# debugging_board_3.net
KiCad netlist of a schematic drawn in Altium Designer
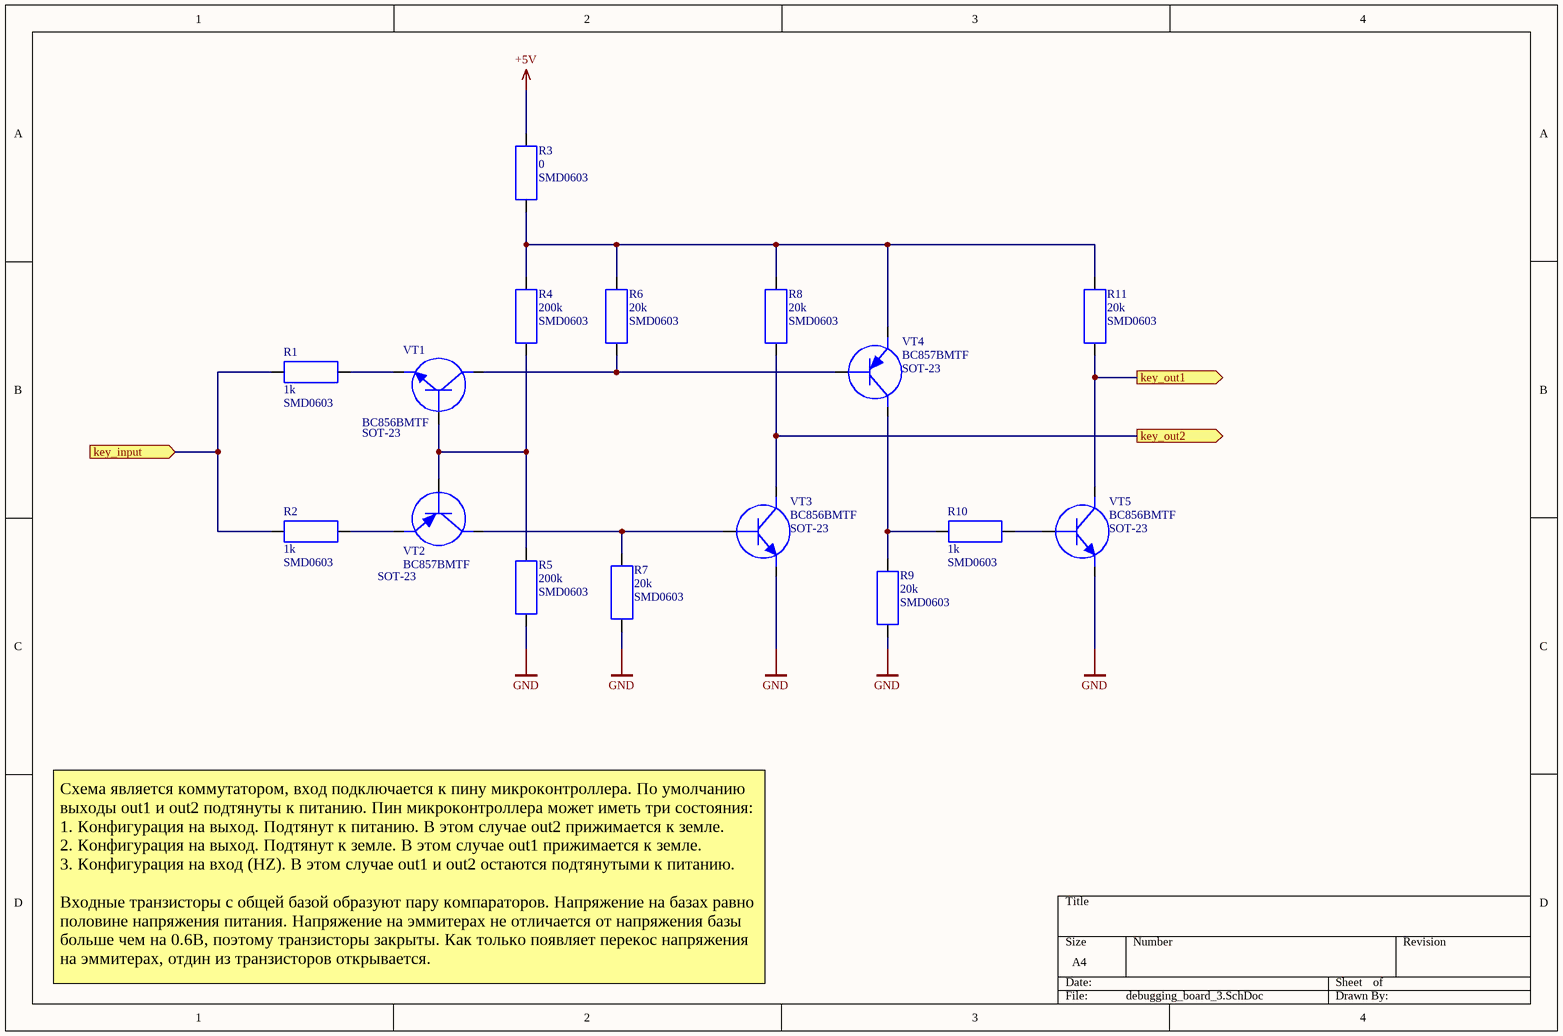
[diagram p0: debugging_board_3.SchDoc]

(export (version "E")
  (design (tool "Eeschema 10.0.6"))
  (components
    (comp (ref "R1")
      (value "1k")
      (footprint "SMD0603(1005)")
      (fields (field (name "PACKAGE") "SMD0603"))
      (libsource (lib "MechanikLibrary") (part "R_0603"))
    )
    (comp (ref "R2")
      (value "1k")
      (footprint "SMD0603(1005)")
      (fields (field (name "PACKAGE") "SMD0603"))
      (libsource (lib "MechanikLibrary") (part "R_0603"))
    )
    (comp (ref "R3")
      (value "0")
      (footprint "SMD0603(1005)")
      (fields (field (name "PACKAGE") "SMD0603"))
      (libsource (lib "MechanikLibrary") (part "R_0603"))
    )
    (comp (ref "R4")
      (value "200k")
      (footprint "SMD0603(1005)")
      (fields (field (name "PACKAGE") "SMD0603"))
      (libsource (lib "MechanikLibrary") (part "R_0603"))
    )
    (comp (ref "R5")
      (value "200k")
      (footprint "SMD0603(1005)")
      (fields (field (name "PACKAGE") "SMD0603"))
      (libsource (lib "MechanikLibrary") (part "R_0603"))
    )
    (comp (ref "R6")
      (value "20k")
      (footprint "SMD0603(1005)")
      (fields (field (name "PACKAGE") "SMD0603"))
      (libsource (lib "MechanikLibrary") (part "R_0603"))
    )
    (comp (ref "R7")
      (value "20k")
      (footprint "SMD0603(1005)")
      (fields (field (name "PACKAGE") "SMD0603"))
      (libsource (lib "MechanikLibrary") (part "R_0603"))
    )
    (comp (ref "R8")
      (value "20k")
      (footprint "SMD0603(1005)")
      (fields (field (name "PACKAGE") "SMD0603"))
      (libsource (lib "MechanikLibrary") (part "R_0603"))
    )
    (comp (ref "R9")
      (value "20k")
      (footprint "SMD0603(1005)")
      (fields (field (name "PACKAGE") "SMD0603"))
      (libsource (lib "MechanikLibrary") (part "R_0603"))
    )
    (comp (ref "R10")
      (value "1k")
      (footprint "SMD0603(1005)")
      (fields (field (name "PACKAGE") "SMD0603"))
      (libsource (lib "MechanikLibrary") (part "R_0603"))
    )
    (comp (ref "R11")
      (value "20k")
      (footprint "SMD0603(1005)")
      (fields (field (name "PACKAGE") "SMD0603"))
      (libsource (lib "MechanikLibrary") (part "R_0603"))
    )
    (comp (ref "VT1")
      (value "BC856BMTF")
      (footprint "SOT23-3")
      (fields (field (name "PACKAGE") "SOT-23"))
      (libsource (lib "MechanikLibrary") (part "VT_NPN_SOT23_3"))
    )
    (comp (ref "VT2")
      (value "BC857BMTF")
      (footprint "SOT23-3")
      (fields (field (name "PACKAGE") "SOT-23"))
      (libsource (lib "MechanikLibrary") (part "VT_PNP_SOT23_3"))
    )
    (comp (ref "VT3")
      (value "BC856BMTF")
      (footprint "SOT23-3")
      (fields (field (name "PACKAGE") "SOT-23"))
      (libsource (lib "MechanikLibrary") (part "VT_NPN_SOT23_3"))
    )
    (comp (ref "VT4")
      (value "BC857BMTF")
      (footprint "SOT23-3")
      (fields (field (name "PACKAGE") "SOT-23"))
      (libsource (lib "MechanikLibrary") (part "VT_PNP_SOT23_3"))
    )
    (comp (ref "VT5")
      (value "BC856BMTF")
      (footprint "SOT23-3")
      (fields (field (name "PACKAGE") "SOT-23"))
      (libsource (lib "MechanikLibrary") (part "VT_NPN_SOT23_3"))
    )
  )
  (nets
    (net (code "1") (name "+5V") (class "Default") (node (ref "R3") (pin "1") (pintype "passive")))
    (net (code "2") (name "/key_input") (class "Default")
      (node (ref "R1") (pin "2") (pintype "passive"))
      (node (ref "R2") (pin "2") (pintype "passive"))
    )
    (net (code "3") (name "/key_out1") (class "Default")
      (node (ref "R11") (pin "2") (pintype "passive"))
      (node (ref "VT5") (pin "3") (pintype "passive"))
    )
    (net (code "4") (name "/key_out2") (class "Default")
      (node (ref "R8") (pin "2") (pintype "passive"))
      (node (ref "VT3") (pin "3") (pintype "passive"))
    )
    (net (code "5") (name "GND") (class "Default")
      (node (ref "R5") (pin "2") (pintype "passive"))
      (node (ref "R7") (pin "2") (pintype "passive"))
      (node (ref "R9") (pin "2") (pintype "passive"))
      (node (ref "VT3") (pin "2") (pintype "passive"))
      (node (ref "VT5") (pin "2") (pintype "passive"))
    )
    (net (code "6") (name "Net-(R1-Pad1)") (class "Default")
      (node (ref "R1") (pin "1") (pintype "passive"))
      (node (ref "VT1") (pin "2") (pintype "passive"))
    )
    (net (code "7") (name "Net-(R2-Pad1)") (class "Default")
      (node (ref "R2") (pin "1") (pintype "passive"))
      (node (ref "VT2") (pin "2") (pintype "passive"))
    )
    (net (code "8") (name "Net-(R4-Pad2)") (class "Default")
      (node (ref "R4") (pin "2") (pintype "passive"))
      (node (ref "R5") (pin "1") (pintype "passive"))
      (node (ref "VT1") (pin "1") (pintype "passive"))
      (node (ref "VT2") (pin "1") (pintype "passive"))
    )
    (net (code "9") (name "Net-(R6-Pad2)") (class "Default")
      (node (ref "R6") (pin "2") (pintype "passive"))
      (node (ref "VT1") (pin "3") (pintype "passive"))
      (node (ref "VT4") (pin "1") (pintype "passive"))
    )
    (net (code "10") (name "Net-(R7-Pad1)") (class "Default")
      (node (ref "R7") (pin "1") (pintype "passive"))
      (node (ref "VT2") (pin "3") (pintype "passive"))
      (node (ref "VT3") (pin "1") (pintype "passive"))
    )
    (net (code "11") (name "Net-(R10-Pad1)") (class "Default")
      (node (ref "R10") (pin "1") (pintype "passive"))
      (node (ref "VT5") (pin "1") (pintype "passive"))
    )
    (net (code "12") (name "Net-(R10-Pad2)") (class "Default")
      (node (ref "R10") (pin "2") (pintype "passive"))
      (node (ref "R9") (pin "1") (pintype "passive"))
      (node (ref "VT4") (pin "3") (pintype "passive"))
    )
    (net (code "13") (name "Net-(R11-Pad1)") (class "Default")
      (node (ref "R11") (pin "1") (pintype "passive"))
      (node (ref "R3") (pin "2") (pintype "passive"))
      (node (ref "R4") (pin "1") (pintype "passive"))
      (node (ref "R6") (pin "1") (pintype "passive"))
      (node (ref "R8") (pin "1") (pintype "passive"))
      (node (ref "VT4") (pin "2") (pintype "passive"))
    )
  )
)
